# Binary_Blaster_v01.net
KiCad netlist of a schematic drawn in EAGLE
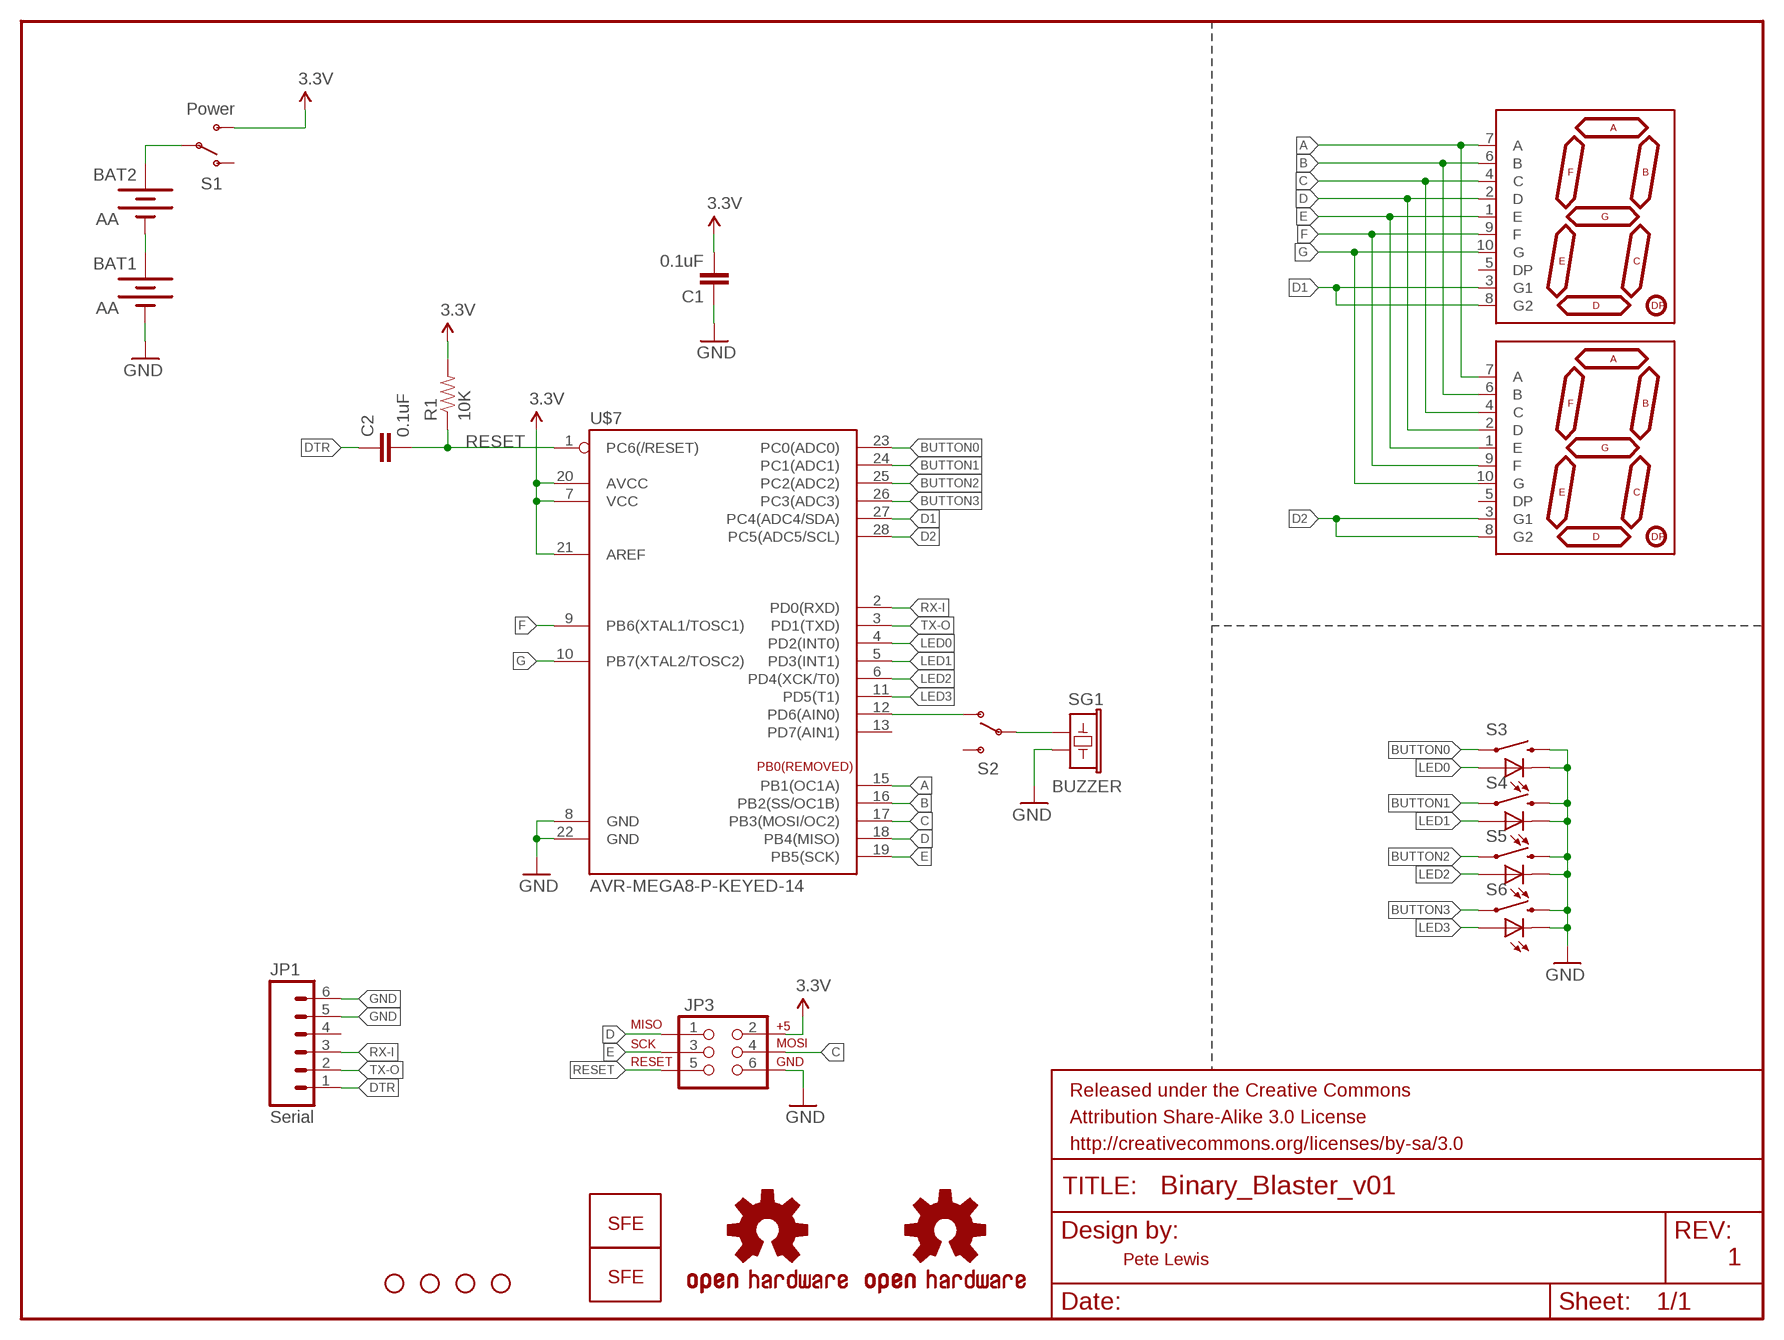
[diagram p0: schematic, sheet 1]

(export (version "E")
  (design (tool "Eeschema 10.0.6"))
  (components
    (comp (ref "BAT1")
      (value "AA")
      (footprint "eagle-import:BATTERY-AA-KIT")
      (libsource (lib "eagle-import") (part "BATTERYAA-KIT"))
    )
    (comp (ref "BAT2")
      (value "AA")
      (footprint "eagle-import:BATTERY-AA-KIT")
      (libsource (lib "eagle-import") (part "BATTERYAA-KIT"))
    )
    (comp (ref "C1")
      (value "0.1uF")
      (footprint "eagle-import:CAP-PTH-SMALL-KIT")
      (libsource (lib "eagle-import") (part "CAPCAP-PTH-SMALL-KIT"))
    )
    (comp (ref "C2")
      (value "0.1uF")
      (footprint "eagle-import:CAP-PTH-SMALL-KIT")
      (libsource (lib "eagle-import") (part "CAPCAP-PTH-SMALL-KIT"))
    )
    (comp (ref "FRAME1")
      (value "FRAME-LETTER")
      (footprint "eagle-import:CREATIVE_COMMONS")
      (libsource (lib "eagle-import") (part "FRAME-LETTER"))
    )
    (comp (ref "JP1")
      (value "Serial")
      (footprint "eagle-import:1X06-NOSILK")
      (libsource (lib "eagle-import") (part "M06-SFENOSILK"))
    )
    (comp (ref "JP2")
      (value "STAND-OFF")
      (footprint "eagle-import:STAND-OFF")
      (libsource (lib "eagle-import") (part "STAND-OFF"))
    )
    (comp (ref "JP3")
      (value "AVR_SPI_PRG_6NS")
      (footprint "eagle-import:2X3-NS")
      (libsource (lib "eagle-import") (part "AVR_SPI_PRG_6NS"))
    )
    (comp (ref "JP5")
      (value "STAND-OFF")
      (footprint "eagle-import:STAND-OFF")
      (libsource (lib "eagle-import") (part "STAND-OFF"))
    )
    (comp (ref "JP6")
      (value "STAND-OFF")
      (footprint "eagle-import:STAND-OFF")
      (libsource (lib "eagle-import") (part "STAND-OFF"))
    )
    (comp (ref "JP7")
      (value "STAND-OFF")
      (footprint "eagle-import:STAND-OFF")
      (libsource (lib "eagle-import") (part "STAND-OFF"))
    )
    (comp (ref "LOGO1")
      (value "LOGO-SFENEW")
      (footprint "eagle-import:SFE-NEW-WEBLOGO")
      (libsource (lib "eagle-import") (part "LOGO-SFENEW"))
    )
    (comp (ref "LOGO2")
      (value "LOGO-SFENEW")
      (footprint "eagle-import:SFE-NEW-WEBLOGO")
      (libsource (lib "eagle-import") (part "LOGO-SFENEW"))
    )
    (comp (ref "R1")
      (value "10K")
      (footprint "eagle-import:AXIAL-0.3-KIT")
      (libsource (lib "eagle-import") (part "RESISTORKIT"))
    )
    (comp (ref "S1")
      (value "Power")
      (footprint "eagle-import:SWITCH-SPDT_KIT")
      (libsource (lib "eagle-import") (part "SWITCH-SPSTKIT"))
    )
    (comp (ref "S2")
      (value "SWITCH-SPSTKIT")
      (footprint "eagle-import:SWITCH-SPDT_KIT")
      (libsource (lib "eagle-import") (part "SWITCH-SPSTKIT"))
    )
    (comp (ref "S3")
      (value "SWITCH-MOMENTARY-LEDPTH")
      (footprint "eagle-import:TACTILE-PTH-LED-12MM")
      (libsource (lib "eagle-import") (part "SWITCH-MOMENTARY-LEDPTH"))
    )
    (comp (ref "S4")
      (value "SWITCH-MOMENTARY-LEDPTH")
      (footprint "eagle-import:TACTILE-PTH-LED-12MM")
      (libsource (lib "eagle-import") (part "SWITCH-MOMENTARY-LEDPTH"))
    )
    (comp (ref "S5")
      (value "SWITCH-MOMENTARY-LEDPTH")
      (footprint "eagle-import:TACTILE-PTH-LED-12MM")
      (libsource (lib "eagle-import") (part "SWITCH-MOMENTARY-LEDPTH"))
    )
    (comp (ref "S6")
      (value "SWITCH-MOMENTARY-LEDPTH")
      (footprint "eagle-import:TACTILE-PTH-LED-12MM")
      (libsource (lib "eagle-import") (part "SWITCH-MOMENTARY-LEDPTH"))
    )
    (comp (ref "SG1")
      (value "BUZZER")
      (footprint "eagle-import:BUZZER-12MM-KIT")
      (libsource (lib "eagle-import") (part "BUZZERKIT"))
    )
    (comp (ref "U$2")
      (value "OSHW-LOGOL")
      (footprint "eagle-import:OSHW-LOGO-L")
      (libsource (lib "eagle-import") (part "OSHW-LOGOL"))
    )
    (comp (ref "U$3")
      (value "OSHW-LOGOS")
      (footprint "eagle-import:OSHW-LOGO-S")
      (libsource (lib "eagle-import") (part "OSHW-LOGOS"))
    )
    (comp (ref "U$4")
      (value "7-SEGMENT-DISPLAYPTH")
      (footprint "eagle-import:7-SEGMENT-DISPLAY")
      (libsource (lib "eagle-import") (part "7-SEGMENT-DISPLAYPTH"))
    )
    (comp (ref "U$5")
      (value "7-SEGMENT-DISPLAYPTH")
      (footprint "eagle-import:7-SEGMENT-DISPLAY")
      (libsource (lib "eagle-import") (part "7-SEGMENT-DISPLAYPTH"))
    )
    (comp (ref "U$7")
      (value "AVR-MEGA8-P-KEYED-14")
      (footprint "eagle-import:DIL28-3_KEYED-14")
      (libsource (lib "eagle-import") (part "AVR-MEGA8-P-KEYED-14"))
    )
  )
  (nets
    (net (code "1") (name "3.3V") (class "Default")
      (node (ref "C1") (pin "2") (pinfunction "2_2") (pintype "passive"))
      (node (ref "JP3") (pin "2") (pinfunction "2_2") (pintype "passive"))
      (node (ref "R1") (pin "P$2") (pinfunction "2_P$2") (pintype "passive"))
      (node (ref "S1") (pin "3") (pinfunction "S_3") (pintype "passive"))
      (node (ref "U$7") (pin "20") (pinfunction "AVCC_20") (pintype "bidirectional"))
      (node (ref "U$7") (pin "21") (pinfunction "AREF_21") (pintype "bidirectional"))
      (node (ref "U$7") (pin "7") (pinfunction "VCC_7") (pintype "bidirectional"))
    )
    (net (code "2") (name "A") (class "Default")
      (node (ref "U$4") (pin "7") (pinfunction "A_7") (pintype "bidirectional"))
      (node (ref "U$5") (pin "7") (pinfunction "A_7") (pintype "bidirectional"))
      (node (ref "U$7") (pin "15") (pinfunction "PB1(OC1A)_15") (pintype "bidirectional"))
    )
    (net (code "3") (name "B") (class "Default")
      (node (ref "U$4") (pin "6") (pinfunction "B_6") (pintype "bidirectional"))
      (node (ref "U$5") (pin "6") (pinfunction "B_6") (pintype "bidirectional"))
      (node (ref "U$7") (pin "16") (pinfunction "PB2(SS/OC1B)_16") (pintype "bidirectional"))
    )
    (net (code "4") (name "BUTTON0") (class "Default")
      (node (ref "S3") (pin "4") (pinfunction "1_4") (pintype "passive"))
      (node (ref "U$7") (pin "23") (pinfunction "PC0(ADC0)_23") (pintype "bidirectional"))
    )
    (net (code "5") (name "BUTTON1") (class "Default")
      (node (ref "S4") (pin "4") (pinfunction "1_4") (pintype "passive"))
      (node (ref "U$7") (pin "24") (pinfunction "PC1(ADC1)_24") (pintype "bidirectional"))
    )
    (net (code "6") (name "BUTTON2") (class "Default")
      (node (ref "S5") (pin "4") (pinfunction "1_4") (pintype "passive"))
      (node (ref "U$7") (pin "25") (pinfunction "PC2(ADC2)_25") (pintype "bidirectional"))
    )
    (net (code "7") (name "BUTTON3") (class "Default")
      (node (ref "S6") (pin "4") (pinfunction "1_4") (pintype "passive"))
      (node (ref "U$7") (pin "26") (pinfunction "PC3(ADC3)_26") (pintype "bidirectional"))
    )
    (net (code "8") (name "C") (class "Default")
      (node (ref "JP3") (pin "4") (pinfunction "4_4") (pintype "passive"))
      (node (ref "U$4") (pin "4") (pinfunction "C_4") (pintype "bidirectional"))
      (node (ref "U$5") (pin "4") (pinfunction "C_4") (pintype "bidirectional"))
      (node (ref "U$7") (pin "17") (pinfunction "PB3(MOSI/OC2)_17") (pintype "bidirectional"))
    )
    (net (code "9") (name "D") (class "Default")
      (node (ref "JP3") (pin "1") (pinfunction "1_1") (pintype "passive"))
      (node (ref "U$4") (pin "2") (pinfunction "D_2") (pintype "bidirectional"))
      (node (ref "U$5") (pin "2") (pinfunction "D_2") (pintype "bidirectional"))
      (node (ref "U$7") (pin "18") (pinfunction "PB4(MISO)_18") (pintype "bidirectional"))
    )
    (net (code "10") (name "D1") (class "Default")
      (node (ref "U$5") (pin "3") (pinfunction "G1_3") (pintype "bidirectional"))
      (node (ref "U$5") (pin "8") (pinfunction "G2_8") (pintype "bidirectional"))
      (node (ref "U$7") (pin "27") (pinfunction "PC4(ADC4/SDA)_27") (pintype "bidirectional"))
    )
    (net (code "11") (name "D2") (class "Default")
      (node (ref "U$4") (pin "3") (pinfunction "G1_3") (pintype "bidirectional"))
      (node (ref "U$4") (pin "8") (pinfunction "G2_8") (pintype "bidirectional"))
      (node (ref "U$7") (pin "28") (pinfunction "PC5(ADC5/SCL)_28") (pintype "bidirectional"))
    )
    (net (code "12") (name "DTR") (class "Default")
      (node (ref "C2") (pin "1") (pinfunction "1_1") (pintype "passive"))
      (node (ref "JP1") (pin "1") (pinfunction "1_1") (pintype "passive"))
    )
    (net (code "13") (name "E") (class "Default")
      (node (ref "JP3") (pin "3") (pinfunction "3_3") (pintype "passive"))
      (node (ref "U$4") (pin "1") (pinfunction "E_1") (pintype "bidirectional"))
      (node (ref "U$5") (pin "1") (pinfunction "E_1") (pintype "bidirectional"))
      (node (ref "U$7") (pin "19") (pinfunction "PB5(SCK)_19") (pintype "bidirectional"))
    )
    (net (code "14") (name "F") (class "Default")
      (node (ref "U$4") (pin "9") (pinfunction "F_9") (pintype "bidirectional"))
      (node (ref "U$5") (pin "9") (pinfunction "F_9") (pintype "bidirectional"))
      (node (ref "U$7") (pin "9") (pinfunction "PB6(XTAL1/TOSC1)_9") (pintype "bidirectional"))
    )
    (net (code "15") (name "G") (class "Default")
      (node (ref "U$4") (pin "10") (pinfunction "G_10") (pintype "bidirectional"))
      (node (ref "U$5") (pin "10") (pinfunction "G_10") (pintype "bidirectional"))
      (node (ref "U$7") (pin "10") (pinfunction "PB7(XTAL2/TOSC2)_10") (pintype "bidirectional"))
    )
    (net (code "16") (name "GND") (class "Default")
      (node (ref "BAT1") (pin "GND@1") (pinfunction "-_GND@1") (pintype "power_in"))
      (node (ref "C1") (pin "1") (pinfunction "1_1") (pintype "passive"))
      (node (ref "JP1") (pin "5") (pinfunction "5_5") (pintype "passive"))
      (node (ref "JP1") (pin "6") (pinfunction "6_6") (pintype "passive"))
      (node (ref "JP3") (pin "6") (pinfunction "6_6") (pintype "passive"))
      (node (ref "S3") (pin "2") (pinfunction "2_2") (pintype "passive"))
      (node (ref "S3") (pin "C") (pinfunction "C_C") (pintype "passive"))
      (node (ref "S4") (pin "2") (pinfunction "2_2") (pintype "passive"))
      (node (ref "S4") (pin "C") (pinfunction "C_C") (pintype "passive"))
      (node (ref "S5") (pin "2") (pinfunction "2_2") (pintype "passive"))
      (node (ref "S5") (pin "C") (pinfunction "C_C") (pintype "passive"))
      (node (ref "S6") (pin "2") (pinfunction "2_2") (pintype "passive"))
      (node (ref "S6") (pin "C") (pinfunction "C_C") (pintype "passive"))
      (node (ref "SG1") (pin "-") (pinfunction "2_-") (pintype "passive"))
      (node (ref "U$7") (pin "22") (pinfunction "GND_22") (pintype "bidirectional"))
      (node (ref "U$7") (pin "8") (pinfunction "GND_8") (pintype "bidirectional"))
    )
    (net (code "17") (name "LED0") (class "Default")
      (node (ref "S3") (pin "A") (pinfunction "A_A") (pintype "passive"))
      (node (ref "U$7") (pin "4") (pinfunction "PD2(INT0)_4") (pintype "bidirectional"))
    )
    (net (code "18") (name "LED1") (class "Default")
      (node (ref "S4") (pin "A") (pinfunction "A_A") (pintype "passive"))
      (node (ref "U$7") (pin "5") (pinfunction "PD3(INT1)_5") (pintype "bidirectional"))
    )
    (net (code "19") (name "LED2") (class "Default")
      (node (ref "S5") (pin "A") (pinfunction "A_A") (pintype "passive"))
      (node (ref "U$7") (pin "6") (pinfunction "PD4(XCK/T0)_6") (pintype "bidirectional"))
    )
    (net (code "20") (name "LED3") (class "Default")
      (node (ref "S6") (pin "A") (pinfunction "A_A") (pintype "passive"))
      (node (ref "U$7") (pin "11") (pinfunction "PD5(T1)_11") (pintype "bidirectional"))
    )
    (net (code "21") (name "Net-(BAT1-+)") (class "Default")
      (node (ref "BAT1") (pin "PWR@1") (pinfunction "+_PWR@1") (pintype "power_in"))
      (node (ref "BAT2") (pin "GND@1") (pinfunction "-_GND@1") (pintype "power_in"))
    )
    (net (code "22") (name "Net-(BAT2-+)") (class "Default")
      (node (ref "BAT2") (pin "PWR@1") (pinfunction "+_PWR@1") (pintype "power_in"))
      (node (ref "S1") (pin "2") (pinfunction "P_2") (pintype "passive"))
    )
    (net (code "23") (name "Net-(S2-O)") (class "Default")
      (node (ref "S2") (pin "1") (pinfunction "O_1") (pintype "passive"))
      (node (ref "U$7") (pin "12") (pinfunction "PD6(AIN0)_12") (pintype "bidirectional"))
    )
    (net (code "24") (name "Net-(S2-P)") (class "Default")
      (node (ref "S2") (pin "2") (pinfunction "P_2") (pintype "passive"))
      (node (ref "SG1") (pin "+") (pinfunction "1_+") (pintype "passive"))
    )
    (net (code "25") (name "RESET") (class "Default")
      (node (ref "C2") (pin "2") (pinfunction "2_2") (pintype "passive"))
      (node (ref "JP3") (pin "5") (pinfunction "5_5") (pintype "passive"))
      (node (ref "R1") (pin "P$1") (pinfunction "1_P$1") (pintype "passive"))
      (node (ref "U$7") (pin "1") (pinfunction "PC6(/RESET)_1") (pintype "bidirectional"))
    )
    (net (code "26") (name "RX-I") (class "Default")
      (node (ref "JP1") (pin "3") (pinfunction "3_3") (pintype "passive"))
      (node (ref "U$7") (pin "2") (pinfunction "PD0(RXD)_2") (pintype "bidirectional"))
    )
    (net (code "27") (name "TX-O") (class "Default")
      (node (ref "JP1") (pin "2") (pinfunction "2_2") (pintype "passive"))
      (node (ref "U$7") (pin "3") (pinfunction "PD1(TXD)_3") (pintype "bidirectional"))
    )
    (net (code "28") (name "unconnected-(JP1-Pad4)") (class "Default")
      (node (ref "JP1") (pin "4") (pinfunction "4_4") (pintype "passive"))
    )
    (net (code "29") (name "unconnected-(S1-O-Pad1)") (class "Default")
      (node (ref "S1") (pin "1") (pinfunction "O_1") (pintype "passive"))
    )
    (net (code "30") (name "unconnected-(S2-S-Pad3)") (class "Default")
      (node (ref "S2") (pin "3") (pinfunction "S_3") (pintype "passive"))
    )
    (net (code "31") (name "unconnected-(U$4-DP-Pad5)") (class "Default")
      (node (ref "U$4") (pin "5") (pinfunction "DP_5") (pintype "bidirectional"))
    )
    (net (code "32") (name "unconnected-(U$5-DP-Pad5)") (class "Default")
      (node (ref "U$5") (pin "5") (pinfunction "DP_5") (pintype "bidirectional"))
    )
    (net (code "33") (name "unconnected-(U$7-PD7(AIN1)-Pad13)") (class "Default")
      (node (ref "U$7") (pin "13") (pinfunction "PD7(AIN1)_13") (pintype "bidirectional"))
    )
  )
)
